# RS232.net
KiCad netlist of a schematic drawn in Altium Designer
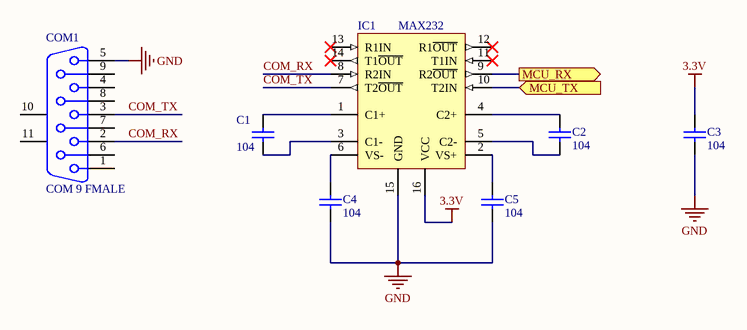
[diagram p0: RS232.SchDoc]

(export (version "E")
  (design (tool "Eeschema 10.0.6"))
  (components
    (comp (ref "C1")
      (value "104")
      (footprint "tu 0805")
      (description "Dán")
      (libsource (lib "Altium_Lib_by_KhueNguyenCreator") (part "Tu 0805 104 50V 10%"))
    )
    (comp (ref "C2")
      (value "104")
      (footprint "tu 0805")
      (description "Dán")
      (libsource (lib "Altium_Lib_by_KhueNguyenCreator") (part "Tu 0805 104 50V 10%"))
    )
    (comp (ref "C3")
      (value "104")
      (footprint "tu 0805")
      (description "Dán")
      (libsource (lib "Altium_Lib_by_KhueNguyenCreator") (part "Tu 0805 104 50V 10%"))
    )
    (comp (ref "C4")
      (value "104")
      (footprint "tu 0805")
      (description "Dán")
      (libsource (lib "Altium_Lib_by_KhueNguyenCreator") (part "Tu 0805 104 50V 10%"))
    )
    (comp (ref "C5")
      (value "104")
      (footprint "tu 0805")
      (description "Dán")
      (libsource (lib "Altium_Lib_by_KhueNguyenCreator") (part "Tu 0805 104 50V 10%"))
    )
    (comp (ref "COM1")
      (value "COM 9 FMALE")
      (footprint "DSB 9-F")
      (description "COM 9")
      (fields (field (name "PUBLISHER") "Altium Limited"))
      (libsource (lib "syhaunguyen") (part "DSB9F"))
    )
    (comp (ref "IC1")
      (value "MAX232")
      (footprint "SO-G16")
      (description "Dual EIA-232 Driver/Receiver")
      (libsource (lib "syhaunguyen") (part "MAX232"))
    )
  )
  (nets
    (net (code "2") (name "/COM_RX") (class "Default")
      (node (ref "COM1") (pin "2") (pinfunction "2_2") (pintype "passive"))
      (node (ref "IC1") (pin "8") (pinfunction "R2IN_8") (pintype "input"))
    )
    (net (code "3") (name "/COM_TX") (class "Default")
      (node (ref "COM1") (pin "3") (pinfunction "3_3") (pintype "passive"))
      (node (ref "IC1") (pin "7") (pinfunction "T2~{OUT}_7") (pintype "output"))
    )
    (net (code "4") (name "/MCU_RX") (class "Default")
      (node (ref "IC1") (pin "9") (pinfunction "R2~{OUT}_9") (pintype "output"))
    )
    (net (code "5") (name "/MCU_TX") (class "Default")
      (node (ref "IC1") (pin "10") (pinfunction "T2IN_10") (pintype "input"))
    )
    (net (code "6") (name "3.3V") (class "Default")
      (node (ref "C3") (pin "1") (pinfunction "1_1") (pintype "passive"))
      (node (ref "IC1") (pin "16") (pinfunction "VCC_16") (pintype "power_in"))
    )
    (net (code "7") (name "GND") (class "Default")
      (node (ref "C3") (pin "2") (pinfunction "2_2") (pintype "passive"))
      (node (ref "C4") (pin "2") (pinfunction "2_2") (pintype "passive"))
      (node (ref "C5") (pin "2") (pinfunction "2_2") (pintype "passive"))
      (node (ref "COM1") (pin "5") (pinfunction "5_5") (pintype "passive"))
      (node (ref "IC1") (pin "15") (pinfunction "GND_15") (pintype "power_in"))
    )
    (net (code "8") (name "Net-(IC1-C1+)") (class "Default")
      (node (ref "C1") (pin "1") (pinfunction "1_1") (pintype "passive"))
      (node (ref "IC1") (pin "1") (pinfunction "C1+_1") (pintype "passive"))
    )
    (net (code "9") (name "Net-(IC1-C1-)") (class "Default")
      (node (ref "C1") (pin "2") (pinfunction "2_2") (pintype "passive"))
      (node (ref "IC1") (pin "3") (pinfunction "C1-_3") (pintype "passive"))
    )
    (net (code "10") (name "Net-(IC1-C2+)") (class "Default")
      (node (ref "C2") (pin "1") (pinfunction "1_1") (pintype "passive"))
      (node (ref "IC1") (pin "4") (pinfunction "C2+_4") (pintype "passive"))
    )
    (net (code "11") (name "Net-(IC1-C2-)") (class "Default")
      (node (ref "C2") (pin "2") (pinfunction "2_2") (pintype "passive"))
      (node (ref "IC1") (pin "5") (pinfunction "C2-_5") (pintype "passive"))
    )
    (net (code "12") (name "Net-(IC1-VS+)") (class "Default")
      (node (ref "C5") (pin "1") (pinfunction "1_1") (pintype "passive"))
      (node (ref "IC1") (pin "2") (pinfunction "VS+_2") (pintype "power_in"))
    )
    (net (code "13") (name "Net-(IC1-VS-)") (class "Default")
      (node (ref "C4") (pin "1") (pinfunction "1_1") (pintype "passive"))
      (node (ref "IC1") (pin "6") (pinfunction "VS-_6") (pintype "power_in"))
    )
    (net (code "14") (name "unconnected-(COM1-MH1-Pad10)") (class "Default")
      (node (ref "COM1") (pin "10") (pinfunction "MH1_10") (pintype "passive"))
    )
    (net (code "15") (name "unconnected-(COM1-MH2-Pad11)") (class "Default")
      (node (ref "COM1") (pin "11") (pinfunction "MH2_11") (pintype "passive"))
    )
    (net (code "16") (name "unconnected-(COM1-Pad1)") (class "Default")
      (node (ref "COM1") (pin "1") (pinfunction "1_1") (pintype "passive"))
    )
    (net (code "17") (name "unconnected-(COM1-Pad4)") (class "Default")
      (node (ref "COM1") (pin "4") (pinfunction "4_4") (pintype "passive"))
    )
    (net (code "18") (name "unconnected-(COM1-Pad6)") (class "Default")
      (node (ref "COM1") (pin "6") (pinfunction "6_6") (pintype "passive"))
    )
    (net (code "19") (name "unconnected-(COM1-Pad7)") (class "Default")
      (node (ref "COM1") (pin "7") (pinfunction "7_7") (pintype "passive"))
    )
    (net (code "20") (name "unconnected-(COM1-Pad8)") (class "Default")
      (node (ref "COM1") (pin "8") (pinfunction "8_8") (pintype "passive"))
    )
    (net (code "21") (name "unconnected-(COM1-Pad9)") (class "Default")
      (node (ref "COM1") (pin "9") (pinfunction "9_9") (pintype "passive"))
    )
    (net (code "22") (name "unconnected-(IC1-R1IN-Pad13)") (class "Default")
      (node (ref "IC1") (pin "13") (pinfunction "R1IN_13") (pintype "input+no_connect"))
    )
    (net (code "23") (name "unconnected-(IC1-R1~{OUT}-Pad12)") (class "Default")
      (node (ref "IC1") (pin "12") (pinfunction "R1~{OUT}_12") (pintype "output+no_connect"))
    )
    (net (code "24") (name "unconnected-(IC1-T1IN-Pad11)") (class "Default")
      (node (ref "IC1") (pin "11") (pinfunction "T1IN_11") (pintype "input+no_connect"))
    )
    (net (code "25") (name "unconnected-(IC1-T1~{OUT}-Pad14)") (class "Default")
      (node (ref "IC1") (pin "14") (pinfunction "T1~{OUT}_14") (pintype "output+no_connect"))
    )
  )
)
